# xmega-a3u-header.net
KiCad netlist of a schematic drawn in EAGLE
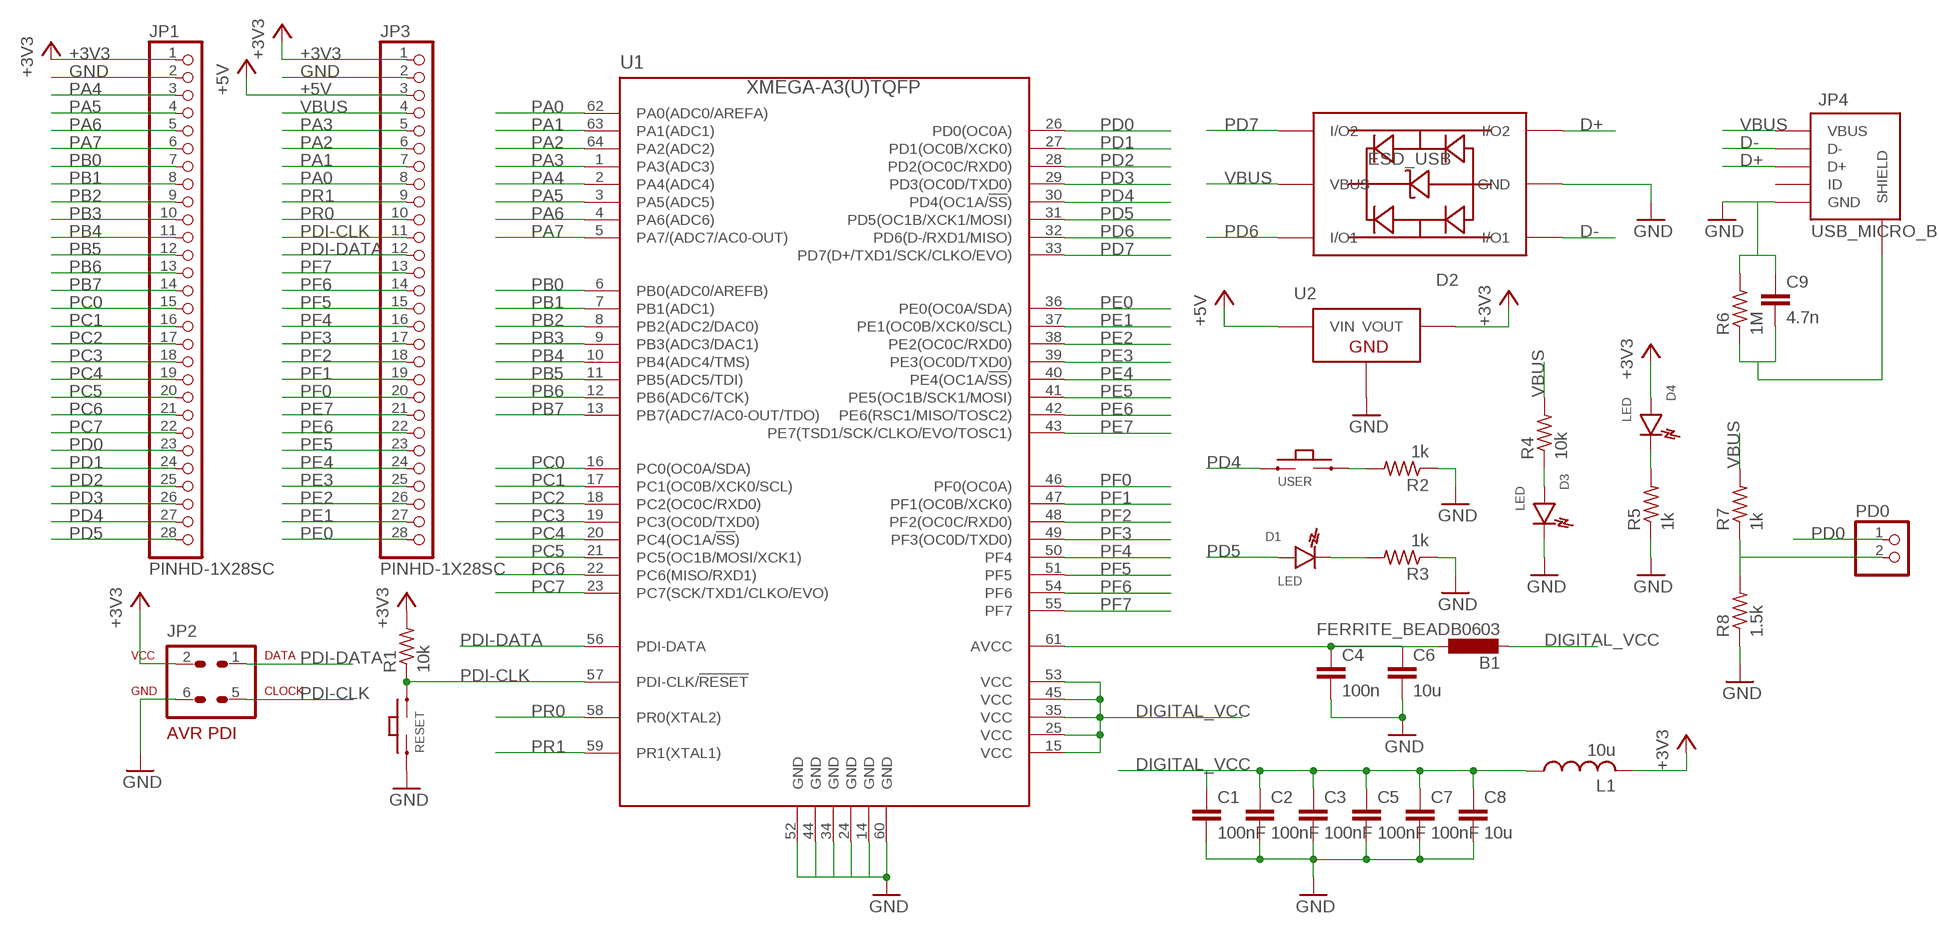
[diagram p0: schematic, sheet 1]

(export (version "E")
  (design (tool "Eeschema 10.0.6"))
  (components
    (comp (ref "B1")
      (value "FERRITE_BEADB0603")
      (footprint "eagle-import:B0603")
      (libsource (lib "eagle-import") (part "FERRITE_BEADB0603"))
    )
    (comp (ref "C1")
      (value "100nF")
      (footprint "eagle-import:C1206")
      (libsource (lib "eagle-import") (part "C-EUC1206"))
    )
    (comp (ref "C2")
      (value "100nF")
      (footprint "eagle-import:C1206")
      (libsource (lib "eagle-import") (part "C-EUC1206"))
    )
    (comp (ref "C3")
      (value "100nF")
      (footprint "eagle-import:C1206")
      (libsource (lib "eagle-import") (part "C-EUC1206"))
    )
    (comp (ref "C4")
      (value "100n")
      (footprint "eagle-import:C1206")
      (libsource (lib "eagle-import") (part "C-EUC1206"))
    )
    (comp (ref "C5")
      (value "100nF")
      (footprint "eagle-import:C1206")
      (libsource (lib "eagle-import") (part "C-EUC1206"))
    )
    (comp (ref "C6")
      (value "10u")
      (footprint "eagle-import:C1206")
      (libsource (lib "eagle-import") (part "C-EUC1206"))
    )
    (comp (ref "C7")
      (value "100nF")
      (footprint "eagle-import:C1206")
      (libsource (lib "eagle-import") (part "C-EUC1206"))
    )
    (comp (ref "C8")
      (value "10u")
      (footprint "eagle-import:C1206")
      (libsource (lib "eagle-import") (part "C-EUC1206"))
    )
    (comp (ref "C9")
      (value "4.7n")
      (footprint "eagle-import:C1206")
      (libsource (lib "eagle-import") (part "C-EUC1206"))
    )
    (comp (ref "D1")
      (value "LED")
      (footprint "eagle-import:1210K")
      (libsource (lib "eagle-import") (part "LED"))
    )
    (comp (ref "D2")
      (value "ESD_USB")
      (footprint "eagle-import:SOT23-6")
      (libsource (lib "eagle-import") (part "ESD_USB"))
    )
    (comp (ref "D3")
      (value "LED")
      (footprint "eagle-import:1210K")
      (libsource (lib "eagle-import") (part "LED"))
    )
    (comp (ref "D4")
      (value "LED")
      (footprint "eagle-import:1210K")
      (libsource (lib "eagle-import") (part "LED"))
    )
    (comp (ref "JP1")
      (value "PINHD-1X28SC")
      (footprint "eagle-import:1X28C")
      (libsource (lib "eagle-import") (part "PINHD-1X28SC"))
    )
    (comp (ref "JP2")
      (value "AVR-PDIVERT")
      (footprint "eagle-import:AVR-ISP-6")
      (libsource (lib "eagle-import") (part "AVR-PDIVERT"))
    )
    (comp (ref "JP3")
      (value "PINHD-1X28SC")
      (footprint "eagle-import:1X28C")
      (libsource (lib "eagle-import") (part "PINHD-1X28SC"))
    )
    (comp (ref "JP4")
      (value "USB_MICRO_B")
      (footprint "eagle-import:USB3076-30-A")
      (libsource (lib "eagle-import") (part "USB_MICRO_B"))
    )
    (comp (ref "L1")
      (value "10u")
      (footprint "eagle-import:L0603")
      (libsource (lib "eagle-import") (part "L-USL0603"))
    )
    (comp (ref "PD0")
      (value "PINHD-1X2")
      (footprint "eagle-import:1X02")
      (libsource (lib "eagle-import") (part "PINHD-1X2"))
    )
    (comp (ref "R1")
      (value "10k")
      (footprint "eagle-import:R1206")
      (libsource (lib "eagle-import") (part "R-US_R1206"))
    )
    (comp (ref "R2")
      (value "1k")
      (footprint "eagle-import:R1206")
      (libsource (lib "eagle-import") (part "R-US_R1206"))
    )
    (comp (ref "R3")
      (value "1k")
      (footprint "eagle-import:R1206")
      (libsource (lib "eagle-import") (part "R-US_R1206"))
    )
    (comp (ref "R4")
      (value "10k")
      (footprint "eagle-import:R1206")
      (libsource (lib "eagle-import") (part "R-US_R1206"))
    )
    (comp (ref "R5")
      (value "1k")
      (footprint "eagle-import:R1206")
      (libsource (lib "eagle-import") (part "R-US_R1206"))
    )
    (comp (ref "R6")
      (value "1M")
      (footprint "eagle-import:R1206")
      (libsource (lib "eagle-import") (part "R-US_R1206"))
    )
    (comp (ref "R7")
      (value "1k")
      (footprint "eagle-import:R1206")
      (libsource (lib "eagle-import") (part "R-US_R1206"))
    )
    (comp (ref "R8")
      (value "1.5k")
      (footprint "eagle-import:R1206")
      (libsource (lib "eagle-import") (part "R-US_R1206"))
    )
    (comp (ref "RESET")
      (value "TACTILE-BUTTONSMD-2PIN")
      (footprint "eagle-import:FSMSM")
      (libsource (lib "eagle-import") (part "TACTILE-BUTTONSMD-2PIN"))
    )
    (comp (ref "U1")
      (value "XMEGA-A3(U)TQFP")
      (footprint "eagle-import:TQFP64")
      (libsource (lib "eagle-import") (part "XMEGA-A3(U)TQFP"))
    )
    (comp (ref "U2")
      (value "AMS1117")
      (footprint "eagle-import:SOT223TAB")
      (libsource (lib "eagle-import") (part "AMS1117"))
    )
    (comp (ref "USER")
      (value "TACTILE-BUTTONSMD-2PIN")
      (footprint "eagle-import:FSMSM")
      (libsource (lib "eagle-import") (part "TACTILE-BUTTONSMD-2PIN"))
    )
  )
  (nets
    (net (code "1") (name "+3V3") (class "Default")
      (node (ref "D4") (pin "POS") (pinfunction "POS_POS") (pintype "bidirectional"))
      (node (ref "JP1") (pin "1") (pinfunction "1_1") (pintype "passive"))
      (node (ref "JP2") (pin "2") (pinfunction "2_2") (pintype "passive"))
      (node (ref "JP3") (pin "1") (pinfunction "1_1") (pintype "passive"))
      (node (ref "L1") (pin "2") (pinfunction "2_2") (pintype "passive"))
      (node (ref "R1") (pin "2") (pinfunction "2_2") (pintype "passive"))
      (node (ref "U2") (pin "2") (pinfunction "VOUT_2") (pintype "power_in"))
      (node (ref "U2") (pin "4") (pinfunction "VOUT_4") (pintype "power_in"))
    )
    (net (code "2") (name "+5V") (class "Default")
      (node (ref "JP3") (pin "3") (pinfunction "3_3") (pintype "passive"))
      (node (ref "U2") (pin "3") (pinfunction "VIN_3") (pintype "power_in"))
    )
    (net (code "3") (name "/D+") (class "Default")
      (node (ref "D2") (pin "3") (pinfunction "I/O2_3") (pintype "bidirectional"))
      (node (ref "JP4") (pin "D+") (pinfunction "D+_D+") (pintype "bidirectional"))
    )
    (net (code "4") (name "/D-") (class "Default")
      (node (ref "D2") (pin "1") (pinfunction "I/O1_1") (pintype "bidirectional"))
      (node (ref "JP4") (pin "D-") (pinfunction "D-_D-") (pintype "bidirectional"))
    )
    (net (code "5") (name "/DIGITAL_VCC") (class "Default")
      (node (ref "B1") (pin "2") (pinfunction "2_2") (pintype "passive"))
      (node (ref "C1") (pin "1") (pinfunction "1_1") (pintype "passive"))
      (node (ref "C2") (pin "1") (pinfunction "1_1") (pintype "passive"))
      (node (ref "C3") (pin "1") (pinfunction "1_1") (pintype "passive"))
      (node (ref "C5") (pin "1") (pinfunction "1_1") (pintype "passive"))
      (node (ref "C7") (pin "1") (pinfunction "1_1") (pintype "passive"))
      (node (ref "C8") (pin "1") (pinfunction "1_1") (pintype "passive"))
      (node (ref "L1") (pin "1") (pinfunction "1_1") (pintype "passive"))
      (node (ref "U1") (pin "15") (pinfunction "VCC_15") (pintype "power_in"))
      (node (ref "U1") (pin "25") (pinfunction "VCC_25") (pintype "power_in"))
      (node (ref "U1") (pin "35") (pinfunction "VCC_35") (pintype "power_in"))
      (node (ref "U1") (pin "45") (pinfunction "VCC_45") (pintype "power_in"))
      (node (ref "U1") (pin "53") (pinfunction "VCC_53") (pintype "power_in"))
    )
    (net (code "6") (name "/PA0") (class "Default")
      (node (ref "JP3") (pin "8") (pinfunction "8_8") (pintype "passive"))
      (node (ref "U1") (pin "62") (pinfunction "PA0(ADC0/AREFA)_62") (pintype "bidirectional"))
    )
    (net (code "7") (name "/PA1") (class "Default")
      (node (ref "JP3") (pin "7") (pinfunction "7_7") (pintype "passive"))
      (node (ref "U1") (pin "63") (pinfunction "PA1(ADC1)_63") (pintype "bidirectional"))
    )
    (net (code "8") (name "/PA2") (class "Default")
      (node (ref "JP3") (pin "6") (pinfunction "6_6") (pintype "passive"))
      (node (ref "U1") (pin "64") (pinfunction "PA2(ADC2)_64") (pintype "bidirectional"))
    )
    (net (code "9") (name "/PA3") (class "Default")
      (node (ref "JP3") (pin "5") (pinfunction "5_5") (pintype "passive"))
      (node (ref "U1") (pin "1") (pinfunction "PA3(ADC3)_1") (pintype "bidirectional"))
    )
    (net (code "10") (name "/PA4") (class "Default")
      (node (ref "JP1") (pin "3") (pinfunction "3_3") (pintype "passive"))
      (node (ref "U1") (pin "2") (pinfunction "PA4(ADC4)_2") (pintype "bidirectional"))
    )
    (net (code "11") (name "/PA5") (class "Default")
      (node (ref "JP1") (pin "4") (pinfunction "4_4") (pintype "passive"))
      (node (ref "U1") (pin "3") (pinfunction "PA5(ADC5)_3") (pintype "bidirectional"))
    )
    (net (code "12") (name "/PA6") (class "Default")
      (node (ref "JP1") (pin "5") (pinfunction "5_5") (pintype "passive"))
      (node (ref "U1") (pin "4") (pinfunction "PA6(ADC6)_4") (pintype "bidirectional"))
    )
    (net (code "13") (name "/PA7") (class "Default")
      (node (ref "JP1") (pin "6") (pinfunction "6_6") (pintype "passive"))
      (node (ref "U1") (pin "5") (pinfunction "PA7/(ADC7/AC0-OUT)_5") (pintype "bidirectional"))
    )
    (net (code "14") (name "/PB0") (class "Default")
      (node (ref "JP1") (pin "7") (pinfunction "7_7") (pintype "passive"))
      (node (ref "U1") (pin "6") (pinfunction "PB0(ADC0/AREFB)_6") (pintype "bidirectional"))
    )
    (net (code "15") (name "/PB1") (class "Default")
      (node (ref "JP1") (pin "8") (pinfunction "8_8") (pintype "passive"))
      (node (ref "U1") (pin "7") (pinfunction "PB1(ADC1)_7") (pintype "bidirectional"))
    )
    (net (code "16") (name "/PB2") (class "Default")
      (node (ref "JP1") (pin "9") (pinfunction "9_9") (pintype "passive"))
      (node (ref "U1") (pin "8") (pinfunction "PB2(ADC2/DAC0)_8") (pintype "bidirectional"))
    )
    (net (code "17") (name "/PB3") (class "Default")
      (node (ref "JP1") (pin "10") (pinfunction "10_10") (pintype "passive"))
      (node (ref "U1") (pin "9") (pinfunction "PB3(ADC3/DAC1)_9") (pintype "bidirectional"))
    )
    (net (code "18") (name "/PB4") (class "Default")
      (node (ref "JP1") (pin "11") (pinfunction "11_11") (pintype "passive"))
      (node (ref "U1") (pin "10") (pinfunction "PB4(ADC4/TMS)_10") (pintype "bidirectional"))
    )
    (net (code "19") (name "/PB5") (class "Default")
      (node (ref "JP1") (pin "12") (pinfunction "12_12") (pintype "passive"))
      (node (ref "U1") (pin "11") (pinfunction "PB5(ADC5/TDI)_11") (pintype "bidirectional"))
    )
    (net (code "20") (name "/PB6") (class "Default")
      (node (ref "JP1") (pin "13") (pinfunction "13_13") (pintype "passive"))
      (node (ref "U1") (pin "12") (pinfunction "PB6(ADC6/TCK)_12") (pintype "bidirectional"))
    )
    (net (code "21") (name "/PB7") (class "Default")
      (node (ref "JP1") (pin "14") (pinfunction "14_14") (pintype "passive"))
      (node (ref "U1") (pin "13") (pinfunction "PB7(ADC7/AC0-OUT/TDO)_13") (pintype "bidirectional"))
    )
    (net (code "22") (name "/PC0") (class "Default")
      (node (ref "JP1") (pin "15") (pinfunction "15_15") (pintype "passive"))
      (node (ref "U1") (pin "16") (pinfunction "PC0(OC0A/SDA)_16") (pintype "bidirectional"))
    )
    (net (code "23") (name "/PC1") (class "Default")
      (node (ref "JP1") (pin "16") (pinfunction "16_16") (pintype "passive"))
      (node (ref "U1") (pin "17") (pinfunction "PC1(OC0B/XCK0/SCL)_17") (pintype "bidirectional"))
    )
    (net (code "24") (name "/PC2") (class "Default")
      (node (ref "JP1") (pin "17") (pinfunction "17_17") (pintype "passive"))
      (node (ref "U1") (pin "18") (pinfunction "PC2(OC0C/RXD0)_18") (pintype "bidirectional"))
    )
    (net (code "25") (name "/PC3") (class "Default")
      (node (ref "JP1") (pin "18") (pinfunction "18_18") (pintype "passive"))
      (node (ref "U1") (pin "19") (pinfunction "PC3(OC0D/TXD0)_19") (pintype "bidirectional"))
    )
    (net (code "26") (name "/PC4") (class "Default")
      (node (ref "JP1") (pin "19") (pinfunction "19_19") (pintype "passive"))
      (node (ref "U1") (pin "20") (pinfunction "PC4(OC1A/~{SS})_20") (pintype "bidirectional"))
    )
    (net (code "27") (name "/PC5") (class "Default")
      (node (ref "JP1") (pin "20") (pinfunction "20_20") (pintype "passive"))
      (node (ref "U1") (pin "21") (pinfunction "PC5(OC1B/MOSI/XCK1)_21") (pintype "bidirectional"))
    )
    (net (code "28") (name "/PC6") (class "Default")
      (node (ref "JP1") (pin "21") (pinfunction "21_21") (pintype "passive"))
      (node (ref "U1") (pin "22") (pinfunction "PC6(MISO/RXD1)_22") (pintype "bidirectional"))
    )
    (net (code "29") (name "/PC7") (class "Default")
      (node (ref "JP1") (pin "22") (pinfunction "22_22") (pintype "passive"))
      (node (ref "U1") (pin "23") (pinfunction "PC7(SCK/TXD1/CLKO/EVO)_23") (pintype "bidirectional"))
    )
    (net (code "30") (name "/PD0") (class "Default")
      (node (ref "JP1") (pin "23") (pinfunction "23_23") (pintype "passive"))
      (node (ref "PD0") (pin "1") (pinfunction "1_1") (pintype "passive"))
      (node (ref "U1") (pin "26") (pinfunction "PD0(OC0A)_26") (pintype "bidirectional"))
    )
    (net (code "31") (name "/PD1") (class "Default")
      (node (ref "JP1") (pin "24") (pinfunction "24_24") (pintype "passive"))
      (node (ref "U1") (pin "27") (pinfunction "PD1(OC0B/XCK0)_27") (pintype "bidirectional"))
    )
    (net (code "32") (name "/PD2") (class "Default")
      (node (ref "JP1") (pin "25") (pinfunction "25_25") (pintype "passive"))
      (node (ref "U1") (pin "28") (pinfunction "PD2(OC0C/RXD0)_28") (pintype "bidirectional"))
    )
    (net (code "33") (name "/PD3") (class "Default")
      (node (ref "JP1") (pin "26") (pinfunction "26_26") (pintype "passive"))
      (node (ref "U1") (pin "29") (pinfunction "PD3(OC0D/TXD0)_29") (pintype "bidirectional"))
    )
    (net (code "34") (name "/PD4") (class "Default")
      (node (ref "JP1") (pin "27") (pinfunction "27_27") (pintype "passive"))
      (node (ref "U1") (pin "30") (pinfunction "PD4(OC1A/~{SS})_30") (pintype "bidirectional"))
      (node (ref "USER") (pin "1") (pinfunction "1_1") (pintype "bidirectional"))
    )
    (net (code "35") (name "/PD5") (class "Default")
      (node (ref "D1") (pin "POS") (pinfunction "POS_POS") (pintype "bidirectional"))
      (node (ref "JP1") (pin "28") (pinfunction "28_28") (pintype "passive"))
      (node (ref "U1") (pin "31") (pinfunction "PD5(OC1B/XCK1/MOSI)_31") (pintype "bidirectional"))
    )
    (net (code "36") (name "/PD6") (class "Default")
      (node (ref "D2") (pin "6") (pinfunction "I/O1_6") (pintype "bidirectional"))
      (node (ref "U1") (pin "32") (pinfunction "PD6(D-/RXD1/MISO)_32") (pintype "bidirectional"))
    )
    (net (code "37") (name "/PD7") (class "Default")
      (node (ref "D2") (pin "4") (pinfunction "I/O2_4") (pintype "bidirectional"))
      (node (ref "U1") (pin "33") (pinfunction "PD7(D+/TXD1/SCK/CLKO/EVO)_33") (pintype "bidirectional"))
    )
    (net (code "38") (name "/PDI-CLK") (class "Default")
      (node (ref "JP2") (pin "5") (pinfunction "5_5") (pintype "passive"))
      (node (ref "JP3") (pin "11") (pinfunction "11_11") (pintype "passive"))
      (node (ref "R1") (pin "1") (pinfunction "1_1") (pintype "passive"))
      (node (ref "RESET") (pin "2") (pinfunction "2_2") (pintype "bidirectional"))
      (node (ref "U1") (pin "57") (pinfunction "PDI-CLK/~{RESET}_57") (pintype "input"))
    )
    (net (code "39") (name "/PDI-DATA") (class "Default")
      (node (ref "JP2") (pin "1") (pinfunction "1_1") (pintype "passive"))
      (node (ref "JP3") (pin "12") (pinfunction "12_12") (pintype "passive"))
      (node (ref "U1") (pin "56") (pinfunction "PDI-DATA_56") (pintype "bidirectional"))
    )
    (net (code "40") (name "/PE0") (class "Default")
      (node (ref "JP3") (pin "28") (pinfunction "28_28") (pintype "passive"))
      (node (ref "U1") (pin "36") (pinfunction "PE0(OC0A/SDA)_36") (pintype "bidirectional"))
    )
    (net (code "41") (name "/PE1") (class "Default")
      (node (ref "JP3") (pin "27") (pinfunction "27_27") (pintype "passive"))
      (node (ref "U1") (pin "37") (pinfunction "PE1(OC0B/XCK0/SCL)_37") (pintype "bidirectional"))
    )
    (net (code "42") (name "/PE2") (class "Default")
      (node (ref "JP3") (pin "26") (pinfunction "26_26") (pintype "passive"))
      (node (ref "U1") (pin "38") (pinfunction "PE2(OC0C/RXD0)_38") (pintype "bidirectional"))
    )
    (net (code "43") (name "/PE3") (class "Default")
      (node (ref "JP3") (pin "25") (pinfunction "25_25") (pintype "passive"))
      (node (ref "U1") (pin "39") (pinfunction "PE3(OC0D/TXD0)_39") (pintype "bidirectional"))
    )
    (net (code "44") (name "/PE4") (class "Default")
      (node (ref "JP3") (pin "24") (pinfunction "24_24") (pintype "passive"))
      (node (ref "U1") (pin "40") (pinfunction "PE4(OC1A/~{SS})_40") (pintype "bidirectional"))
    )
    (net (code "45") (name "/PE5") (class "Default")
      (node (ref "JP3") (pin "23") (pinfunction "23_23") (pintype "passive"))
      (node (ref "U1") (pin "41") (pinfunction "PE5(OC1B/SCK1/MOSI)_41") (pintype "bidirectional"))
    )
    (net (code "46") (name "/PE6") (class "Default")
      (node (ref "JP3") (pin "22") (pinfunction "22_22") (pintype "passive"))
      (node (ref "U1") (pin "42") (pinfunction "PE6(RSC1/MISO/TOSC2)_42") (pintype "bidirectional"))
    )
    (net (code "47") (name "/PE7") (class "Default")
      (node (ref "JP3") (pin "21") (pinfunction "21_21") (pintype "passive"))
      (node (ref "U1") (pin "43") (pinfunction "PE7(TSD1/SCK/CLKO/EVO/TOSC1)_43") (pintype "bidirectional"))
    )
    (net (code "48") (name "/PF0") (class "Default")
      (node (ref "JP3") (pin "20") (pinfunction "20_20") (pintype "passive"))
      (node (ref "U1") (pin "46") (pinfunction "PF0(OC0A)_46") (pintype "bidirectional"))
    )
    (net (code "49") (name "/PF1") (class "Default")
      (node (ref "JP3") (pin "19") (pinfunction "19_19") (pintype "passive"))
      (node (ref "U1") (pin "47") (pinfunction "PF1(OC0B/XCK0)_47") (pintype "bidirectional"))
    )
    (net (code "50") (name "/PF2") (class "Default")
      (node (ref "JP3") (pin "18") (pinfunction "18_18") (pintype "passive"))
      (node (ref "U1") (pin "48") (pinfunction "PF2(OC0C/RXD0)_48") (pintype "bidirectional"))
    )
    (net (code "51") (name "/PF3") (class "Default")
      (node (ref "JP3") (pin "17") (pinfunction "17_17") (pintype "passive"))
      (node (ref "U1") (pin "49") (pinfunction "PF3(OC0D/TXD0)_49") (pintype "bidirectional"))
    )
    (net (code "52") (name "/PF4") (class "Default")
      (node (ref "JP3") (pin "16") (pinfunction "16_16") (pintype "passive"))
      (node (ref "U1") (pin "50") (pinfunction "PF4_50") (pintype "bidirectional"))
    )
    (net (code "53") (name "/PF5") (class "Default")
      (node (ref "JP3") (pin "15") (pinfunction "15_15") (pintype "passive"))
      (node (ref "U1") (pin "51") (pinfunction "PF5_51") (pintype "bidirectional"))
    )
    (net (code "54") (name "/PF6") (class "Default")
      (node (ref "JP3") (pin "14") (pinfunction "14_14") (pintype "passive"))
      (node (ref "U1") (pin "54") (pinfunction "PF6_54") (pintype "bidirectional"))
    )
    (net (code "55") (name "/PF7") (class "Default")
      (node (ref "JP3") (pin "13") (pinfunction "13_13") (pintype "passive"))
      (node (ref "U1") (pin "55") (pinfunction "PF7_55") (pintype "bidirectional"))
    )
    (net (code "56") (name "/PR0") (class "Default")
      (node (ref "JP3") (pin "10") (pinfunction "10_10") (pintype "passive"))
      (node (ref "U1") (pin "58") (pinfunction "PR0(XTAL2)_58") (pintype "bidirectional"))
    )
    (net (code "57") (name "/PR1") (class "Default")
      (node (ref "JP3") (pin "9") (pinfunction "9_9") (pintype "passive"))
      (node (ref "U1") (pin "59") (pinfunction "PR1(XTAL1)_59") (pintype "bidirectional"))
    )
    (net (code "58") (name "/VBUS") (class "Default")
      (node (ref "D2") (pin "5") (pinfunction "VBUS_5") (pintype "power_in"))
      (node (ref "JP3") (pin "4") (pinfunction "4_4") (pintype "passive"))
      (node (ref "JP4") (pin "VBUS") (pinfunction "VBUS_VBUS") (pintype "power_in"))
      (node (ref "R4") (pin "2") (pinfunction "2_2") (pintype "passive"))
      (node (ref "R7") (pin "2") (pinfunction "2_2") (pintype "passive"))
    )
    (net (code "59") (name "GND") (class "Default")
      (node (ref "C1") (pin "2") (pinfunction "2_2") (pintype "passive"))
      (node (ref "C2") (pin "2") (pinfunction "2_2") (pintype "passive"))
      (node (ref "C3") (pin "2") (pinfunction "2_2") (pintype "passive"))
      (node (ref "C4") (pin "2") (pinfunction "2_2") (pintype "passive"))
      (node (ref "C5") (pin "2") (pinfunction "2_2") (pintype "passive"))
      (node (ref "C6") (pin "2") (pinfunction "2_2") (pintype "passive"))
      (node (ref "C7") (pin "2") (pinfunction "2_2") (pintype "passive"))
      (node (ref "C8") (pin "2") (pinfunction "2_2") (pintype "passive"))
      (node (ref "C9") (pin "1") (pinfunction "1_1") (pintype "passive"))
      (node (ref "D2") (pin "2") (pinfunction "GND_2") (pintype "power_in"))
      (node (ref "D3") (pin "NEG") (pinfunction "NEG_NEG") (pintype "bidirectional"))
      (node (ref "JP1") (pin "2") (pinfunction "2_2") (pintype "passive"))
      (node (ref "JP2") (pin "6") (pinfunction "6_6") (pintype "passive"))
      (node (ref "JP3") (pin "2") (pinfunction "2_2") (pintype "passive"))
      (node (ref "JP4") (pin "GND") (pinfunction "GND_GND") (pintype "power_in"))
      (node (ref "R2") (pin "1") (pinfunction "1_1") (pintype "passive"))
      (node (ref "R3") (pin "1") (pinfunction "1_1") (pintype "passive"))
      (node (ref "R5") (pin "1") (pinfunction "1_1") (pintype "passive"))
      (node (ref "R6") (pin "2") (pinfunction "2_2") (pintype "passive"))
      (node (ref "R8") (pin "1") (pinfunction "1_1") (pintype "passive"))
      (node (ref "RESET") (pin "1") (pinfunction "1_1") (pintype "bidirectional"))
      (node (ref "U1") (pin "14") (pinfunction "GND_14") (pintype "power_in"))
      (node (ref "U1") (pin "24") (pinfunction "GND_24") (pintype "power_in"))
      (node (ref "U1") (pin "34") (pinfunction "GND_34") (pintype "power_in"))
      (node (ref "U1") (pin "44") (pinfunction "GND_44") (pintype "power_in"))
      (node (ref "U1") (pin "52") (pinfunction "GND_52") (pintype "power_in"))
      (node (ref "U1") (pin "60") (pinfunction "GND_60") (pintype "power_in"))
      (node (ref "U2") (pin "1") (pinfunction "GND_1") (pintype "power_in"))
    )
    (net (code "60") (name "Net-(C9-Pad2)") (class "Default")
      (node (ref "C9") (pin "2") (pinfunction "2_2") (pintype "passive"))
      (node (ref "JP4") (pin "BIG_PAD_LEFT") (pinfunction "SHIELD_BIG_PAD_LEFT") (pintype "power_in"))
      (node (ref "JP4") (pin "BIG_PAD_RIGHT") (pinfunction "SHIELD_BIG_PAD_RIGHT") (pintype "power_in"))
      (node (ref "JP4") (pin "MECH_RIGHT") (pinfunction "SHIELD_MECH_RIGHT") (pintype "power_in"))
      (node (ref "JP4") (pin "PAD_LEFT") (pinfunction "SHIELD_PAD_LEFT") (pintype "power_in"))
      (node (ref "JP4") (pin "PAD_RIGHT") (pinfunction "SHIELD_PAD_RIGHT") (pintype "power_in"))
      (node (ref "JP4") (pin "SHIELD_LEFT") (pinfunction "SHIELD_SHIELD_LEFT") (pintype "power_in"))
      (node (ref "R6") (pin "1") (pinfunction "1_1") (pintype "passive"))
    )
    (net (code "61") (name "Net-(D1-PadNEG)") (class "Default")
      (node (ref "D1") (pin "NEG") (pinfunction "NEG_NEG") (pintype "bidirectional"))
      (node (ref "R3") (pin "2") (pinfunction "2_2") (pintype "passive"))
    )
    (net (code "62") (name "Net-(D3-PadPOS)") (class "Default")
      (node (ref "D3") (pin "POS") (pinfunction "POS_POS") (pintype "bidirectional"))
      (node (ref "R4") (pin "1") (pinfunction "1_1") (pintype "passive"))
    )
    (net (code "63") (name "Net-(D4-PadNEG)") (class "Default")
      (node (ref "D4") (pin "NEG") (pinfunction "NEG_NEG") (pintype "bidirectional"))
      (node (ref "R5") (pin "2") (pinfunction "2_2") (pintype "passive"))
    )
    (net (code "64") (name "Net-(PD0-Pad2)") (class "Default")
      (node (ref "PD0") (pin "2") (pinfunction "2_2") (pintype "passive"))
      (node (ref "R7") (pin "1") (pinfunction "1_1") (pintype "passive"))
      (node (ref "R8") (pin "2") (pinfunction "2_2") (pintype "passive"))
    )
    (net (code "65") (name "Net-(R2-Pad2)") (class "Default")
      (node (ref "R2") (pin "2") (pinfunction "2_2") (pintype "passive"))
      (node (ref "USER") (pin "2") (pinfunction "2_2") (pintype "bidirectional"))
    )
    (net (code "66") (name "Net-(U1-AVCC)") (class "Default")
      (node (ref "B1") (pin "1") (pinfunction "1_1") (pintype "passive"))
      (node (ref "C4") (pin "1") (pinfunction "1_1") (pintype "passive"))
      (node (ref "C6") (pin "1") (pinfunction "1_1") (pintype "passive"))
      (node (ref "U1") (pin "61") (pinfunction "AVCC_61") (pintype "power_in"))
    )
    (net (code "67") (name "unconnected-(JP4-PadID)") (class "Default")
      (node (ref "JP4") (pin "ID") (pinfunction "ID_ID") (pintype "bidirectional"))
    )
  )
)
